# Remotor.net
KiCad netlist of a schematic drawn in Altium Designer
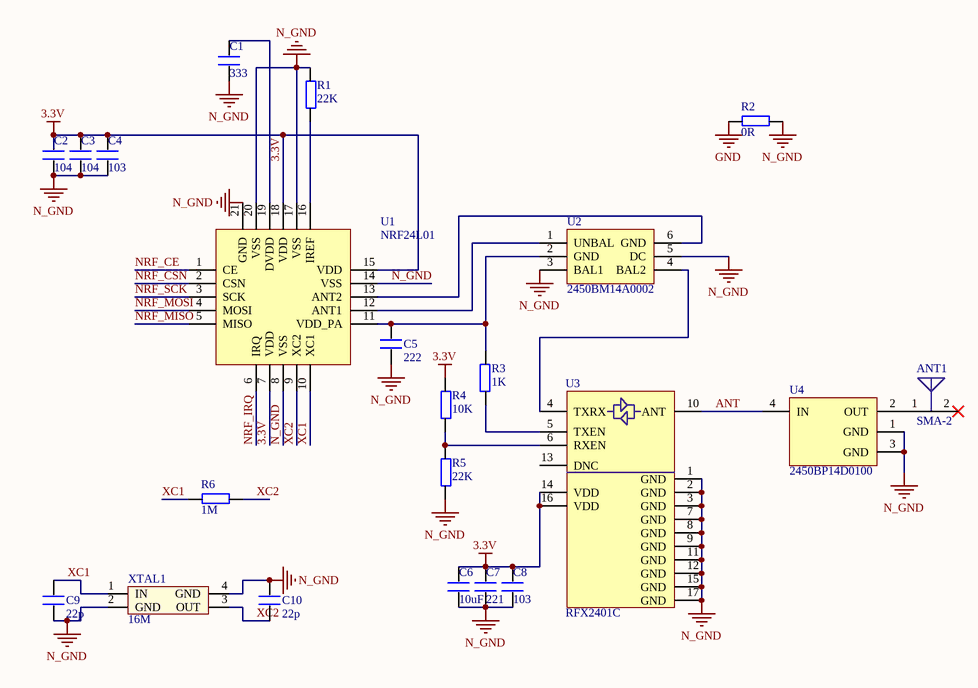
[diagram p0: Remotor.SchDoc]

(export (version "E")
  (design (tool "Eeschema 10.0.6"))
  (components
    (comp (ref "ANT1")
      (value "SMA-2")
      (footprint "SMB")
      (libsource (lib "REMOTOR V1.6") (part "CHIP_ANTENNA"))
    )
    (comp (ref "C1") (value "333") (footprint "0402") (libsource (lib "REMOTOR V1.6") (part "C")))
    (comp (ref "C2") (value "104") (footprint "0402") (libsource (lib "REMOTOR V1.6") (part "C")))
    (comp (ref "C3") (value "104") (footprint "0402") (libsource (lib "REMOTOR V1.6") (part "C")))
    (comp (ref "C4") (value "103") (footprint "0402") (libsource (lib "REMOTOR V1.6") (part "C")))
    (comp (ref "C5") (value "222") (footprint "0402") (libsource (lib "REMOTOR V1.6") (part "C")))
    (comp (ref "C6") (value "10uF") (footprint "0805") (libsource (lib "REMOTOR V1.6") (part "C")))
    (comp (ref "C7") (value "221") (footprint "0402") (libsource (lib "REMOTOR V1.6") (part "C")))
    (comp (ref "C8") (value "103") (footprint "0402") (libsource (lib "REMOTOR V1.6") (part "C")))
    (comp (ref "C9") (value "22p") (footprint "0402") (libsource (lib "REMOTOR V1.6") (part "C")))
    (comp (ref "C10") (value "22p") (footprint "0402") (libsource (lib "REMOTOR V1.6") (part "C")))
    (comp (ref "R1") (value "22K") (footprint "0402") (libsource (lib "REMOTOR V1.6") (part "R")))
    (comp (ref "R2") (value "0R") (footprint "0402") (libsource (lib "REMOTOR V1.6") (part "R")))
    (comp (ref "R3") (value "1K") (footprint "0402") (libsource (lib "REMOTOR V1.6") (part "R")))
    (comp (ref "R4") (value "10K") (footprint "0402") (libsource (lib "REMOTOR V1.6") (part "R")))
    (comp (ref "R5") (value "22K") (footprint "0402") (libsource (lib "REMOTOR V1.6") (part "R")))
    (comp (ref "R6") (value "1M") (footprint "0402") (libsource (lib "REMOTOR V1.6") (part "R")))
    (comp (ref "U1") (value "NRF24L01") (footprint "QFN20") (libsource (lib "REMOTOR V1.6") (part "nrf24xx")))
    (comp (ref "U2") (value "2450BM14A0002") (footprint "0603-6") (libsource (lib "MiniFly ") (part "BALUN")))
    (comp (ref "U3")
      (value "RFX2401C")
      (footprint "QFN16M")
      (libsource (lib "REMOTOR V1.6") (part "RFX2401C"))
    )
    (comp (ref "U4")
      (value "2450BP14D0100")
      (footprint "BALUN_250BP")
      (libsource (lib "REMOTOR V1.6") (part "BALUN_1"))
    )
    (comp (ref "XTAL1")
      (value "16M")
      (footprint "XTAL3225   无源")
      (description "无源贴片晶振")
      (libsource (lib "REMOTOR V1.6") (part "XTAL-无源贴片"))
    )
  )
  (nets
    (net (code "1") (name "/ANT") (class "Default")
      (node (ref "U3") (pin "10") (pinfunction "ANT_10") (pintype "passive"))
      (node (ref "U4") (pin "4") (pinfunction "IN_4") (pintype "passive"))
    )
    (net (code "2") (name "/NRF_CE") (class "Default")
      (node (ref "U1") (pin "1") (pinfunction "CE_1") (pintype "passive"))
    )
    (net (code "3") (name "/NRF_CSN") (class "Default")
      (node (ref "U1") (pin "2") (pinfunction "CSN_2") (pintype "passive"))
    )
    (net (code "4") (name "/NRF_IRQ") (class "Default")
      (node (ref "U1") (pin "6") (pinfunction "IRQ_6") (pintype "passive"))
    )
    (net (code "5") (name "/NRF_MISO") (class "Default")
      (node (ref "U1") (pin "5") (pinfunction "MISO_5") (pintype "passive"))
    )
    (net (code "6") (name "/NRF_MOSI") (class "Default")
      (node (ref "U1") (pin "4") (pinfunction "MOSI_4") (pintype "passive"))
    )
    (net (code "7") (name "/NRF_SCK") (class "Default")
      (node (ref "U1") (pin "3") (pinfunction "SCK_3") (pintype "passive"))
    )
    (net (code "8") (name "/XC1") (class "Default")
      (node (ref "C9") (pin "1") (pintype "passive"))
      (node (ref "R6") (pin "2") (pintype "passive"))
      (node (ref "U1") (pin "10") (pinfunction "XC1_10") (pintype "passive"))
      (node (ref "XTAL1") (pin "1") (pinfunction "IN_1") (pintype "passive"))
    )
    (net (code "9") (name "/XC2") (class "Default")
      (node (ref "C10") (pin "2") (pintype "passive"))
      (node (ref "R6") (pin "1") (pintype "passive"))
      (node (ref "U1") (pin "9") (pinfunction "XC2_9") (pintype "passive"))
      (node (ref "XTAL1") (pin "3") (pinfunction "OUT_3") (pintype "passive"))
    )
    (net (code "10") (name "3.3V") (class "Default")
      (node (ref "C2") (pin "2") (pintype "passive"))
      (node (ref "C3") (pin "2") (pintype "passive"))
      (node (ref "C4") (pin "2") (pintype "passive"))
      (node (ref "C6") (pin "1") (pintype "passive"))
      (node (ref "C7") (pin "1") (pintype "passive"))
      (node (ref "C8") (pin "1") (pintype "passive"))
      (node (ref "R4") (pin "2") (pintype "passive"))
      (node (ref "U1") (pin "15") (pinfunction "VDD_15") (pintype "passive"))
      (node (ref "U1") (pin "18") (pinfunction "VDD_18") (pintype "passive"))
      (node (ref "U1") (pin "7") (pinfunction "VDD_7") (pintype "passive"))
      (node (ref "U3") (pin "14") (pinfunction "VDD_14") (pintype "passive"))
      (node (ref "U3") (pin "16") (pinfunction "VDD_16") (pintype "passive"))
    )
    (net (code "11") (name "GND") (class "Default") (node (ref "R2") (pin "2") (pintype "passive")))
    (net (code "12") (name "N_GND") (class "Default")
      (node (ref "C1") (pin "1") (pintype "passive"))
      (node (ref "C10") (pin "1") (pintype "passive"))
      (node (ref "C2") (pin "1") (pintype "passive"))
      (node (ref "C3") (pin "1") (pintype "passive"))
      (node (ref "C4") (pin "1") (pintype "passive"))
      (node (ref "C5") (pin "2") (pintype "passive"))
      (node (ref "C6") (pin "2") (pintype "passive"))
      (node (ref "C7") (pin "2") (pintype "passive"))
      (node (ref "C8") (pin "2") (pintype "passive"))
      (node (ref "C9") (pin "2") (pintype "passive"))
      (node (ref "R1") (pin "2") (pintype "passive"))
      (node (ref "R2") (pin "1") (pintype "passive"))
      (node (ref "R5") (pin "1") (pintype "passive"))
      (node (ref "U1") (pin "14") (pinfunction "VSS_14") (pintype "passive"))
      (node (ref "U1") (pin "17") (pinfunction "VSS_17") (pintype "passive"))
      (node (ref "U1") (pin "20") (pinfunction "VSS_20") (pintype "passive"))
      (node (ref "U1") (pin "21") (pinfunction "GND_21") (pintype "passive"))
      (node (ref "U1") (pin "8") (pinfunction "VSS_8") (pintype "passive"))
      (node (ref "U2") (pin "3") (pinfunction "BAL1_3") (pintype "passive"))
      (node (ref "U2") (pin "5") (pinfunction "DC_5") (pintype "passive"))
      (node (ref "U3") (pin "1") (pinfunction "GND_1") (pintype "passive"))
      (node (ref "U3") (pin "11") (pinfunction "GND_11") (pintype "passive"))
      (node (ref "U3") (pin "12") (pinfunction "GND_12") (pintype "passive"))
      (node (ref "U3") (pin "15") (pinfunction "GND_15") (pintype "passive"))
      (node (ref "U3") (pin "17") (pinfunction "GND_17") (pintype "passive"))
      (node (ref "U3") (pin "2") (pinfunction "GND_2") (pintype "passive"))
      (node (ref "U3") (pin "3") (pinfunction "GND_3") (pintype "passive"))
      (node (ref "U3") (pin "7") (pinfunction "GND_7") (pintype "passive"))
      (node (ref "U3") (pin "8") (pinfunction "GND_8") (pintype "passive"))
      (node (ref "U3") (pin "9") (pinfunction "GND_9") (pintype "passive"))
      (node (ref "U4") (pin "1") (pinfunction "GND_1") (pintype "passive"))
      (node (ref "U4") (pin "3") (pinfunction "GND_3") (pintype "passive"))
      (node (ref "XTAL1") (pin "2") (pinfunction "GND_2") (pintype "passive"))
      (node (ref "XTAL1") (pin "4") (pinfunction "GND_4") (pintype "passive"))
    )
    (net (code "13") (name "Net-(ANT1-FP)") (class "Default")
      (node (ref "ANT1") (pin "1") (pinfunction "FP_1") (pintype "passive"))
      (node (ref "U4") (pin "2") (pinfunction "OUT_2") (pintype "passive"))
    )
    (net (code "14") (name "Net-(U1-ANT1)") (class "Default")
      (node (ref "U1") (pin "12") (pinfunction "ANT1_12") (pintype "passive"))
      (node (ref "U2") (pin "1") (pinfunction "UNBAL_1") (pintype "passive"))
    )
    (net (code "15") (name "Net-(U1-ANT2)") (class "Default")
      (node (ref "U1") (pin "13") (pinfunction "ANT2_13") (pintype "passive"))
      (node (ref "U2") (pin "6") (pinfunction "GND_6") (pintype "passive"))
    )
    (net (code "16") (name "Net-(U1-DVDD)") (class "Default")
      (node (ref "C1") (pin "2") (pintype "passive"))
      (node (ref "U1") (pin "19") (pinfunction "DVDD_19") (pintype "passive"))
    )
    (net (code "17") (name "Net-(U1-IREF)") (class "Default")
      (node (ref "R1") (pin "1") (pintype "passive"))
      (node (ref "U1") (pin "16") (pinfunction "IREF_16") (pintype "passive"))
    )
    (net (code "18") (name "Net-(U1-VDD_PA)") (class "Default")
      (node (ref "C5") (pin "1") (pintype "passive"))
      (node (ref "R3") (pin "1") (pintype "passive"))
      (node (ref "U1") (pin "11") (pinfunction "VDD_PA_11") (pintype "passive"))
      (node (ref "U2") (pin "2") (pinfunction "GND_2") (pintype "passive"))
    )
    (net (code "19") (name "Net-(U2-BAL2)") (class "Default")
      (node (ref "U2") (pin "4") (pinfunction "BAL2_4") (pintype "passive"))
      (node (ref "U3") (pin "4") (pinfunction "TXRX_4") (pintype "passive"))
    )
    (net (code "20") (name "Net-(U3-RXEN)") (class "Default")
      (node (ref "R4") (pin "1") (pintype "passive"))
      (node (ref "R5") (pin "2") (pintype "passive"))
      (node (ref "U3") (pin "6") (pinfunction "RXEN_6") (pintype "passive"))
    )
    (net (code "21") (name "Net-(U3-TXEN)") (class "Default")
      (node (ref "R3") (pin "2") (pintype "passive"))
      (node (ref "U3") (pin "5") (pinfunction "TXEN_5") (pintype "passive"))
    )
    (net (code "22") (name "unconnected-(ANT1-NC-Pad2)") (class "Default")
      (node (ref "ANT1") (pin "2") (pinfunction "NC_2") (pintype "passive+no_connect"))
    )
    (net (code "23") (name "unconnected-(U3-DNC-Pad13)") (class "Default")
      (node (ref "U3") (pin "13") (pinfunction "DNC_13") (pintype "passive"))
    )
  )
)
